# Sheet1.net
KiCad netlist of a schematic drawn in Altium Designer
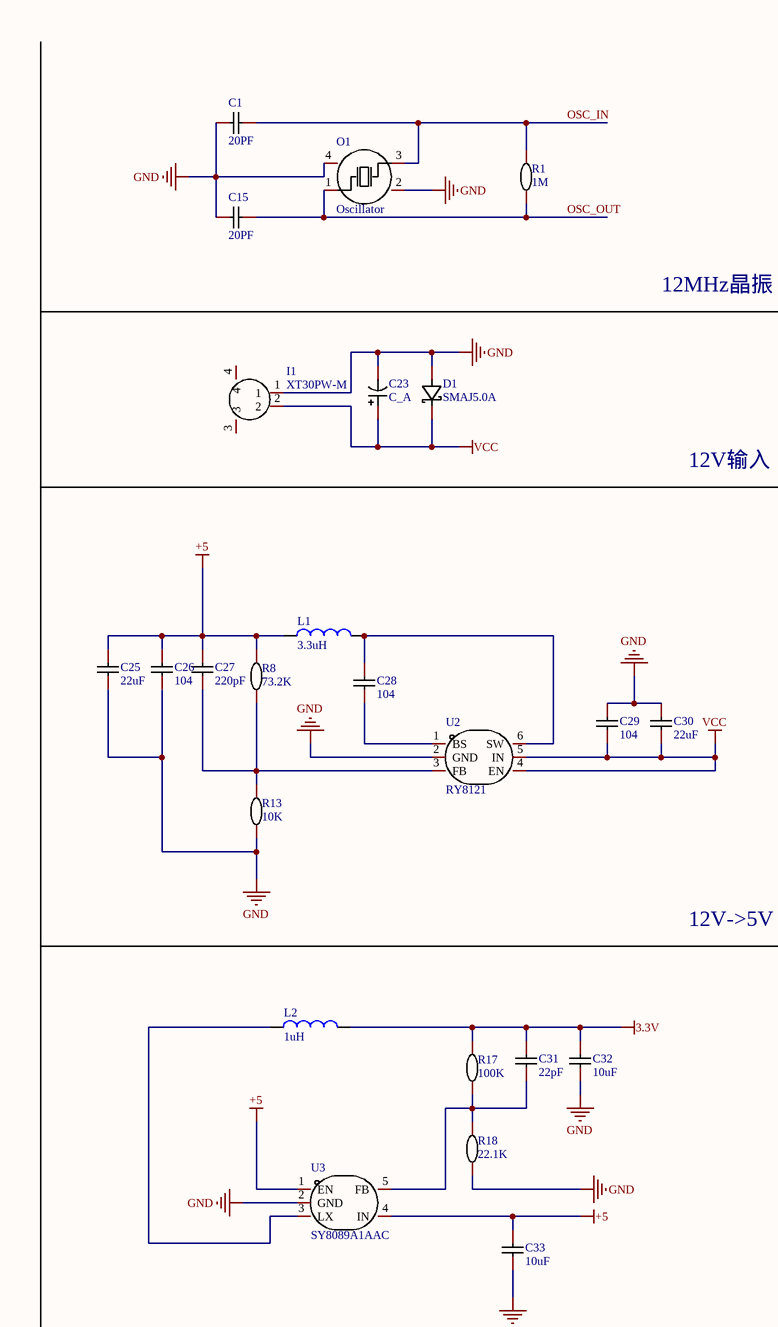
[diagram p0: Sheet1.SchDoc, top left]
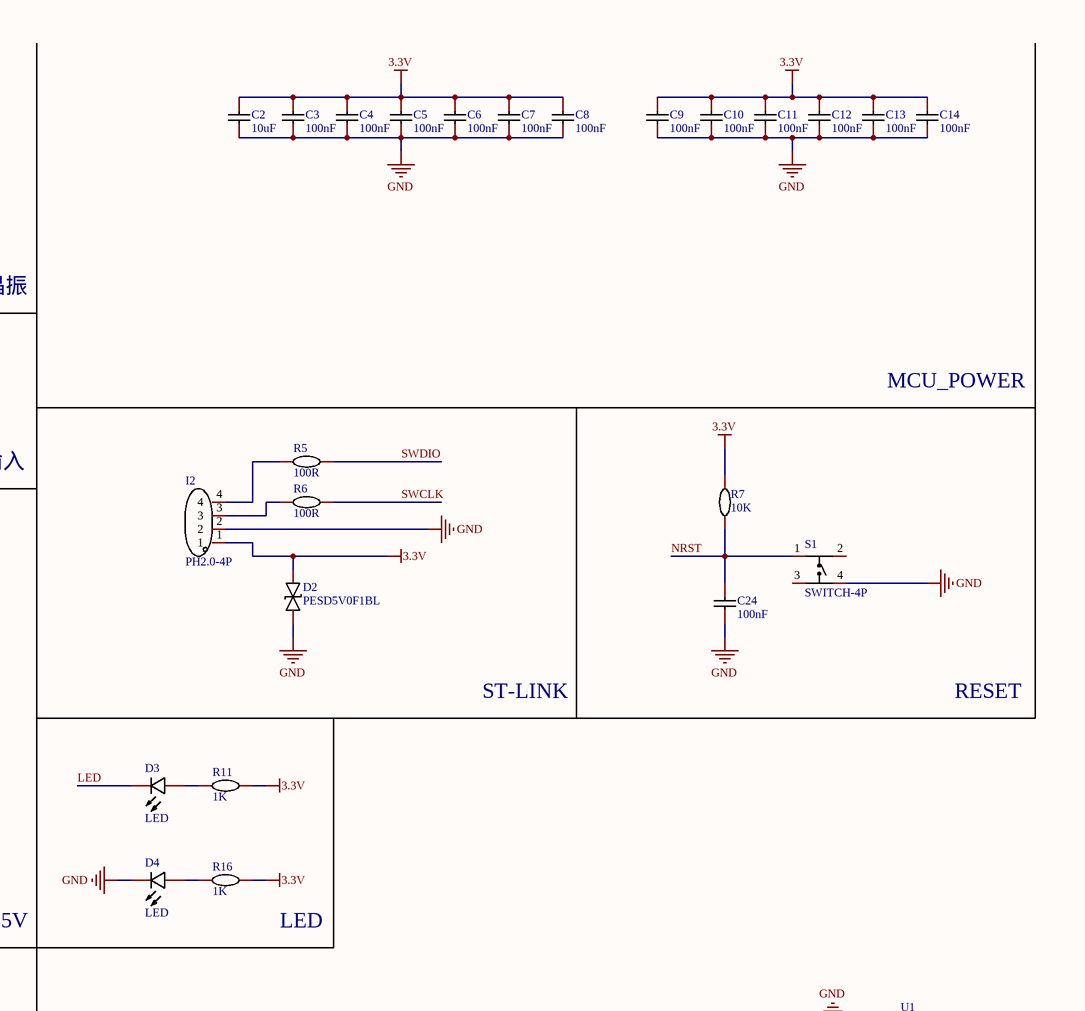
[diagram p1: Sheet1.SchDoc, top right]
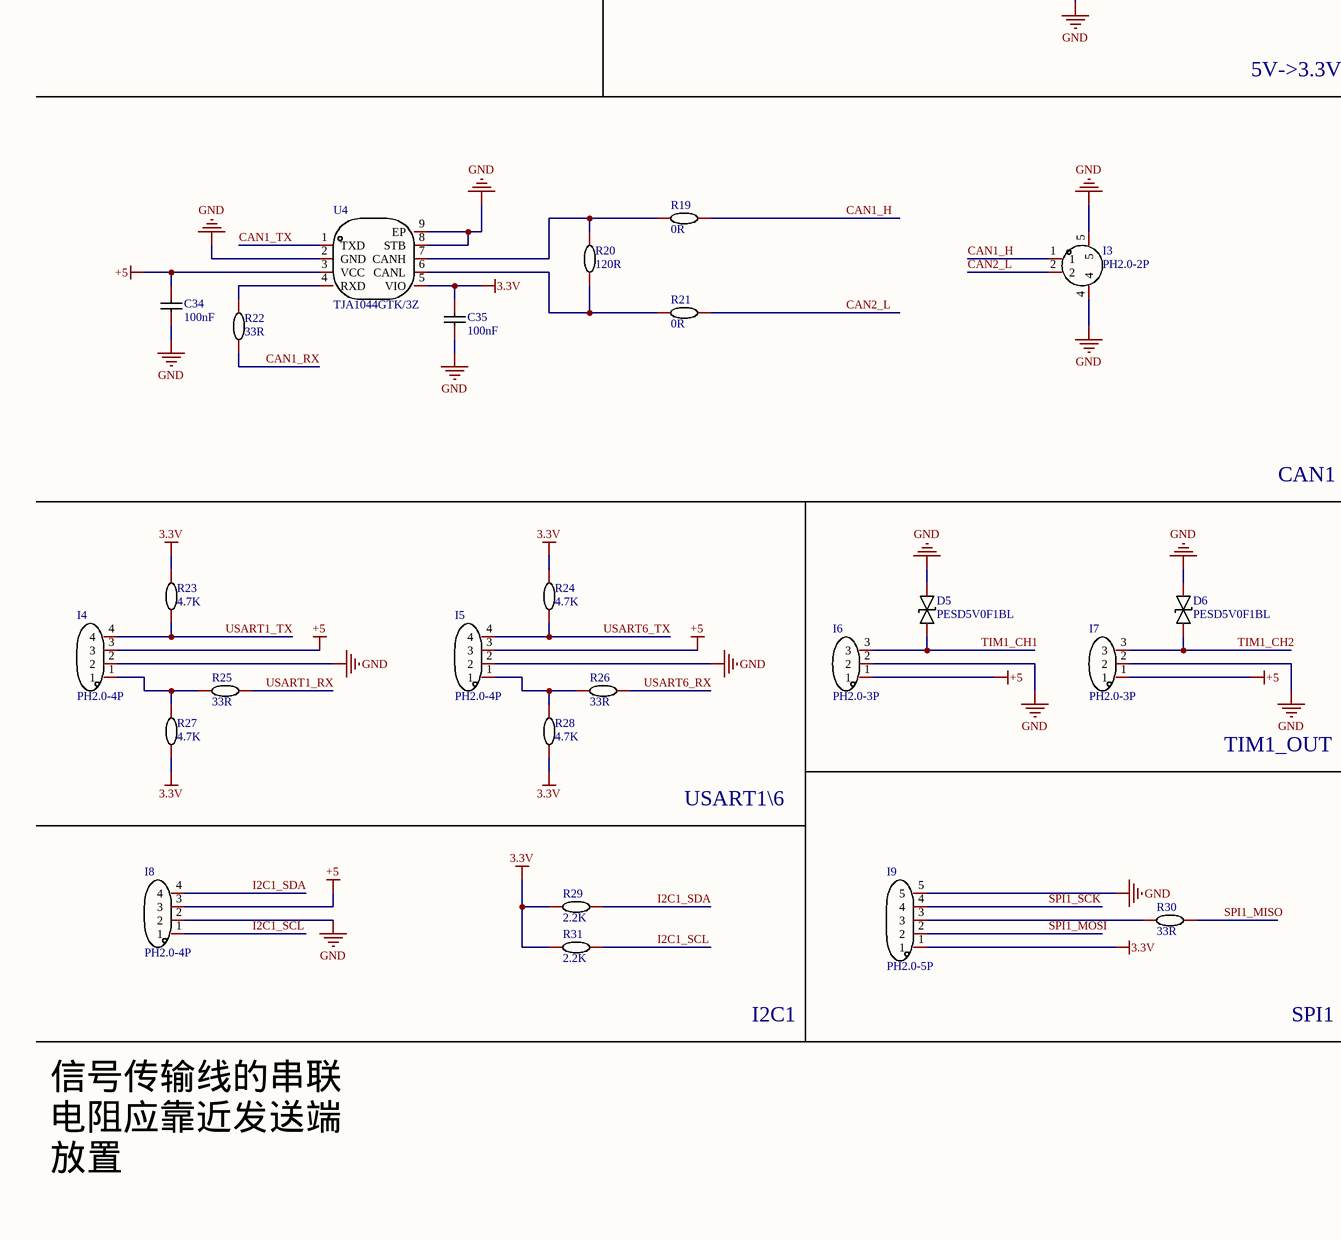
[diagram p2: Sheet1.SchDoc, bottom left]
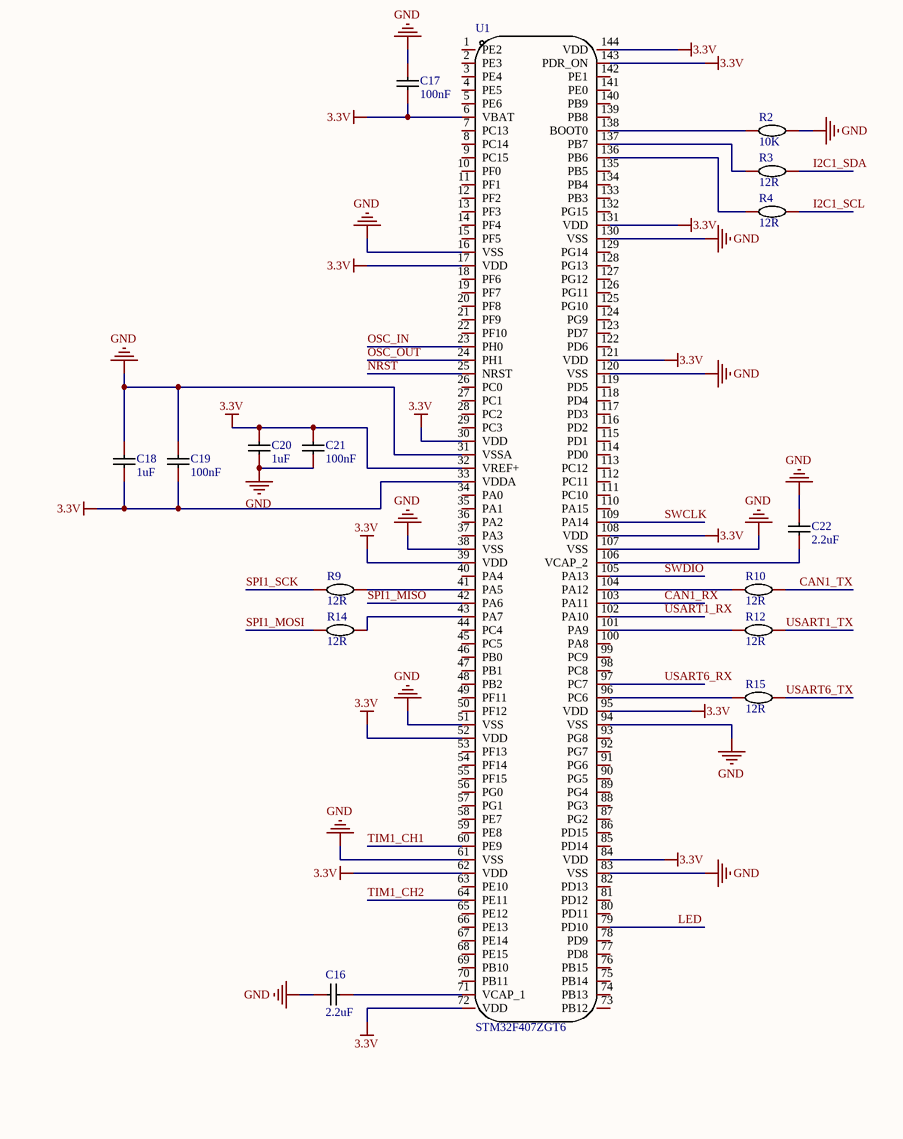
[diagram p3: Sheet1.SchDoc, bottom right]

(export (version "E")
  (design (tool "Eeschema 10.0.6"))
  (components
    (comp (ref "C1")
      (value "20PF")
      (footprint "C_0201")
      (description "贴片电容")
      (libsource (lib "My_Integrated_Library") (part "C"))
    )
    (comp (ref "C2")
      (value "10uF")
      (footprint "C_0201")
      (description "无极性贴片电容")
      (libsource (lib "My_Integrated_Library") (part "C"))
    )
    (comp (ref "C3")
      (value "100nF")
      (footprint "C_0201")
      (description "无极性贴片电容")
      (libsource (lib "My_Integrated_Library") (part "C"))
    )
    (comp (ref "C4")
      (value "100nF")
      (footprint "C_0201")
      (description "无极性贴片电容")
      (libsource (lib "My_Integrated_Library") (part "C"))
    )
    (comp (ref "C5")
      (value "100nF")
      (footprint "C_0201")
      (description "无极性贴片电容")
      (libsource (lib "My_Integrated_Library") (part "C"))
    )
    (comp (ref "C6")
      (value "100nF")
      (footprint "C_0201")
      (description "无极性贴片电容")
      (libsource (lib "My_Integrated_Library") (part "C"))
    )
    (comp (ref "C7")
      (value "100nF")
      (footprint "C_0201")
      (description "无极性贴片电容")
      (libsource (lib "My_Integrated_Library") (part "C"))
    )
    (comp (ref "C8")
      (value "100nF")
      (footprint "C_0201")
      (description "无极性贴片电容")
      (libsource (lib "My_Integrated_Library") (part "C"))
    )
    (comp (ref "C9")
      (value "100nF")
      (footprint "C_0201")
      (description "无极性贴片电容")
      (libsource (lib "My_Integrated_Library") (part "C"))
    )
    (comp (ref "C10")
      (value "100nF")
      (footprint "C_0201")
      (description "无极性贴片电容")
      (libsource (lib "My_Integrated_Library") (part "C"))
    )
    (comp (ref "C11")
      (value "100nF")
      (footprint "C_0201")
      (description "无极性贴片电容")
      (libsource (lib "My_Integrated_Library") (part "C"))
    )
    (comp (ref "C12")
      (value "100nF")
      (footprint "C_0201")
      (description "无极性贴片电容")
      (libsource (lib "My_Integrated_Library") (part "C"))
    )
    (comp (ref "C13")
      (value "100nF")
      (footprint "C_0201")
      (description "无极性贴片电容")
      (libsource (lib "My_Integrated_Library") (part "C"))
    )
    (comp (ref "C14")
      (value "100nF")
      (footprint "C_0201")
      (description "无极性贴片电容")
      (libsource (lib "My_Integrated_Library") (part "C"))
    )
    (comp (ref "C15")
      (value "20PF")
      (footprint "C_0201")
      (description "贴片电容")
      (libsource (lib "My_Integrated_Library") (part "C"))
    )
    (comp (ref "C16")
      (value "2.2uF")
      (footprint "C_0201")
      (description "无极性贴片电容")
      (libsource (lib "My_Integrated_Library") (part "C"))
    )
    (comp (ref "C17")
      (value "100nF")
      (footprint "C_0201")
      (description "无极性贴片电容")
      (libsource (lib "My_Integrated_Library") (part "C"))
    )
    (comp (ref "C18")
      (value "1uF")
      (footprint "C_0201")
      (description "无极性贴片电容")
      (libsource (lib "My_Integrated_Library") (part "C"))
    )
    (comp (ref "C19")
      (value "100nF")
      (footprint "C_0201")
      (description "无极性贴片电容")
      (libsource (lib "My_Integrated_Library") (part "C"))
    )
    (comp (ref "C20")
      (value "1uF")
      (footprint "C_0201")
      (description "无极性贴片电容")
      (libsource (lib "My_Integrated_Library") (part "C"))
    )
    (comp (ref "C21")
      (value "100nF")
      (footprint "C_0201")
      (description "无极性贴片电容")
      (libsource (lib "My_Integrated_Library") (part "C"))
    )
    (comp (ref "C22")
      (value "2.2uF")
      (footprint "C_0201")
      (description "无极性贴片电容")
      (libsource (lib "My_Integrated_Library") (part "C"))
    )
    (comp (ref "C23")
      (value "C_A")
      (footprint "C_8*10.5")
      (description "铝电解电容")
      (libsource (lib "My_Integrated_Library") (part "C_A"))
    )
    (comp (ref "C24")
      (value "100nF")
      (footprint "C_0201")
      (description "无极性贴片电容")
      (libsource (lib "My_Integrated_Library") (part "C"))
    )
    (comp (ref "C25")
      (value "22uF")
      (footprint "C_0402")
      (description "无极性贴片电容")
      (libsource (lib "My_Integrated_Library") (part "C"))
    )
    (comp (ref "C26")
      (value "104")
      (footprint "C_0402")
      (description "无极性贴片电容")
      (libsource (lib "My_Integrated_Library") (part "C"))
    )
    (comp (ref "C27")
      (value "220pF")
      (footprint "C_0402")
      (description "无极性贴片电容")
      (libsource (lib "My_Integrated_Library") (part "C"))
    )
    (comp (ref "C28")
      (value "104")
      (footprint "C_0402")
      (description "无极性贴片电容")
      (libsource (lib "My_Integrated_Library") (part "C"))
    )
    (comp (ref "C29")
      (value "104")
      (footprint "C_0402")
      (description "无极性贴片电容")
      (libsource (lib "My_Integrated_Library") (part "C"))
    )
    (comp (ref "C30")
      (value "22uF")
      (footprint "C_0402")
      (description "无极性贴片电容")
      (libsource (lib "My_Integrated_Library") (part "C"))
    )
    (comp (ref "C31")
      (value "22pF")
      (footprint "C_0603")
      (description "无极性贴片电容")
      (libsource (lib "My_Integrated_Library") (part "C"))
    )
    (comp (ref "C32")
      (value "10uF")
      (footprint "C_0603")
      (description "无极性贴片电容")
      (libsource (lib "My_Integrated_Library") (part "C"))
    )
    (comp (ref "C33")
      (value "10uF")
      (footprint "C_0603")
      (description "无极性贴片电容")
      (libsource (lib "My_Integrated_Library") (part "C"))
    )
    (comp (ref "C34")
      (value "100nF")
      (footprint "C_0402")
      (description "无极性贴片电容")
      (libsource (lib "My_Integrated_Library") (part "C"))
    )
    (comp (ref "C35")
      (value "100nF")
      (footprint "C_0402")
      (description "无极性贴片电容")
      (libsource (lib "My_Integrated_Library") (part "C"))
    )
    (comp (ref "D1")
      (value "SMAJ5.0A")
      (footprint "SMAJ5.0A")
      (description "TVS")
      (libsource (lib "My_Integrated_Library") (part "SMAJ5.0A"))
    )
    (comp (ref "D2")
      (value "PESD5V0F1BL")
      (footprint "PESD5V0F1BL")
      (description "双向TVS")
      (libsource (lib "My_Integrated_Library") (part "PESD5V0F1BL"))
    )
    (comp (ref "D3")
      (value "LED")
      (footprint "LED_0603")
      (description "发光二极管")
      (libsource (lib "My_Integrated_Library") (part "LED"))
    )
    (comp (ref "D4")
      (value "LED")
      (footprint "LED_0603")
      (description "发光二极管")
      (libsource (lib "My_Integrated_Library") (part "LED"))
    )
    (comp (ref "D5")
      (value "PESD5V0F1BL")
      (footprint "PESD5V0F1BL")
      (description "双向TVS")
      (libsource (lib "My_Integrated_Library") (part "PESD5V0F1BL"))
    )
    (comp (ref "D6")
      (value "PESD5V0F1BL")
      (footprint "PESD5V0F1BL")
      (description "双向TVS")
      (libsource (lib "My_Integrated_Library") (part "PESD5V0F1BL"))
    )
    (comp (ref "I1")
      (value "XT30PW-M")
      (footprint "XT30PW-M")
      (description "卧式公头")
      (libsource (lib "My_Integrated_Library") (part "XT30PW-M"))
    )
    (comp (ref "I2")
      (value "PH2.0-4P")
      (footprint "PH2.0-4P")
      (libsource (lib "My_Integrated_Library") (part "PH2.0-4P"))
    )
    (comp (ref "I3")
      (value "PH2.0-2P")
      (footprint "PH2.0-2P")
      (description "卧贴")
      (libsource (lib "My_Integrated_Library") (part "PH2.0-2P"))
    )
    (comp (ref "I4")
      (value "PH2.0-4P")
      (footprint "PH2.0-4P")
      (libsource (lib "My_Integrated_Library") (part "PH2.0-4P"))
    )
    (comp (ref "I5")
      (value "PH2.0-4P")
      (footprint "PH2.0-4P")
      (libsource (lib "My_Integrated_Library") (part "PH2.0-4P"))
    )
    (comp (ref "I6")
      (value "PH2.0-3P")
      (footprint "PH2.0-3P")
      (description "PH3.0-3P弯插")
      (libsource (lib "My_Integrated_Library") (part "PH2.0-3P"))
    )
    (comp (ref "I7")
      (value "PH2.0-3P")
      (footprint "PH2.0-3P")
      (description "PH3.0-3P弯插")
      (libsource (lib "My_Integrated_Library") (part "PH2.0-3P"))
    )
    (comp (ref "I8")
      (value "PH2.0-4P")
      (footprint "PH2.0-4P")
      (libsource (lib "My_Integrated_Library") (part "PH2.0-4P"))
    )
    (comp (ref "I9")
      (value "PH2.0-5P")
      (footprint "PH2.0-5P")
      (description "弯插")
      (libsource (lib "My_Integrated_Library") (part "PH2.0-5P"))
    )
    (comp (ref "L1")
      (value "3.3uH")
      (footprint "L_0402")
      (description "SMD电感4.2*4.2*1.8")
      (libsource (lib "My_Integrated_Library") (part "L"))
    )
    (comp (ref "L2")
      (value "1uH")
      (footprint "L_0402")
      (description "SMD电感4.2*4.2*1.8")
      (libsource (lib "My_Integrated_Library") (part "L"))
    )
    (comp (ref "O1")
      (value "Oscillator")
      (footprint "Oscillator")
      (description "晶振")
      (libsource (lib "My_Integrated_Library") (part "Oscillator"))
    )
    (comp (ref "R1")
      (value "1M")
      (footprint "R_0201")
      (description "电阻")
      (libsource (lib "My_Integrated_Library") (part "R"))
    )
    (comp (ref "R2")
      (value "10K")
      (footprint "R_0402")
      (description "贴片电阻")
      (libsource (lib "My_Integrated_Library") (part "R"))
    )
    (comp (ref "R3")
      (value "12R")
      (footprint "R_0402")
      (description "贴片电阻")
      (libsource (lib "My_Integrated_Library") (part "R"))
    )
    (comp (ref "R4")
      (value "12R")
      (footprint "R_0402")
      (description "贴片电阻")
      (libsource (lib "My_Integrated_Library") (part "R"))
    )
    (comp (ref "R5")
      (value "100R")
      (footprint "R_0201")
      (description "贴片电阻")
      (libsource (lib "My_Integrated_Library") (part "R"))
    )
    (comp (ref "R6")
      (value "100R")
      (footprint "R_0201")
      (description "贴片电阻")
      (libsource (lib "My_Integrated_Library") (part "R"))
    )
    (comp (ref "R7")
      (value "10K")
      (footprint "R_0201")
      (description "贴片电阻")
      (libsource (lib "My_Integrated_Library") (part "R"))
    )
    (comp (ref "R8")
      (value "73.2K")
      (footprint "R_0603")
      (description "贴片电阻")
      (libsource (lib "My_Integrated_Library") (part "R"))
    )
    (comp (ref "R9")
      (value "12R")
      (footprint "R_0402")
      (description "贴片电阻")
      (libsource (lib "My_Integrated_Library") (part "R"))
    )
    (comp (ref "R10")
      (value "12R")
      (footprint "R_0402")
      (description "贴片电阻")
      (libsource (lib "My_Integrated_Library") (part "R"))
    )
    (comp (ref "R11")
      (value "1K")
      (footprint "R_0603")
      (description "贴片电阻")
      (libsource (lib "My_Integrated_Library") (part "R"))
    )
    (comp (ref "R12")
      (value "12R")
      (footprint "R_0402")
      (description "贴片电阻")
      (libsource (lib "My_Integrated_Library") (part "R"))
    )
    (comp (ref "R13")
      (value "10K")
      (footprint "R_0603")
      (description "贴片电阻")
      (libsource (lib "My_Integrated_Library") (part "R"))
    )
    (comp (ref "R14")
      (value "12R")
      (footprint "R_0402")
      (description "贴片电阻")
      (libsource (lib "My_Integrated_Library") (part "R"))
    )
    (comp (ref "R15")
      (value "12R")
      (footprint "R_0402")
      (description "贴片电阻")
      (libsource (lib "My_Integrated_Library") (part "R"))
    )
    (comp (ref "R16")
      (value "1K")
      (footprint "R_0603")
      (description "贴片电阻")
      (libsource (lib "My_Integrated_Library") (part "R"))
    )
    (comp (ref "R17")
      (value "100K")
      (footprint "R_0603")
      (description "贴片电阻")
      (libsource (lib "My_Integrated_Library") (part "R"))
    )
    (comp (ref "R18")
      (value "22.1K")
      (footprint "R_0603")
      (description "贴片电阻")
      (libsource (lib "My_Integrated_Library") (part "R"))
    )
    (comp (ref "R19")
      (value "0R")
      (footprint "R_0402")
      (description "贴片电阻")
      (libsource (lib "My_Integrated_Library") (part "R"))
    )
    (comp (ref "R20")
      (value "120R")
      (footprint "R_0402")
      (description "贴片电阻")
      (libsource (lib "My_Integrated_Library") (part "R"))
    )
    (comp (ref "R21")
      (value "0R")
      (footprint "R_0402")
      (description "贴片电阻")
      (libsource (lib "My_Integrated_Library") (part "R"))
    )
    (comp (ref "R22")
      (value "33R")
      (footprint "R_0402")
      (description "贴片电阻")
      (libsource (lib "My_Integrated_Library") (part "R"))
    )
    (comp (ref "R23")
      (value "4.7K")
      (footprint "R_0402")
      (description "贴片电阻")
      (libsource (lib "My_Integrated_Library") (part "R"))
    )
    (comp (ref "R24")
      (value "4.7K")
      (footprint "R_0402")
      (description "贴片电阻")
      (libsource (lib "My_Integrated_Library") (part "R"))
    )
    (comp (ref "R25")
      (value "33R")
      (footprint "R_0402")
      (description "贴片电阻")
      (libsource (lib "My_Integrated_Library") (part "R"))
    )
    (comp (ref "R26")
      (value "33R")
      (footprint "R_0402")
      (description "贴片电阻")
      (libsource (lib "My_Integrated_Library") (part "R"))
    )
    (comp (ref "R27")
      (value "4.7K")
      (footprint "R_0402")
      (description "贴片电阻")
      (libsource (lib "My_Integrated_Library") (part "R"))
    )
    (comp (ref "R28")
      (value "4.7K")
      (footprint "R_0402")
      (description "贴片电阻")
      (libsource (lib "My_Integrated_Library") (part "R"))
    )
    (comp (ref "R29")
      (value "2.2K")
      (footprint "R_0402")
      (description "贴片电阻")
      (libsource (lib "My_Integrated_Library") (part "R"))
    )
    (comp (ref "R30")
      (value "33R")
      (footprint "R_0402")
      (description "贴片电阻")
      (libsource (lib "My_Integrated_Library") (part "R"))
    )
    (comp (ref "R31")
      (value "2.2K")
      (footprint "R_0402")
      (description "贴片电阻")
      (libsource (lib "My_Integrated_Library") (part "R"))
    )
    (comp (ref "S1")
      (value "SWITCH-4P")
      (footprint "SWITCH-4P")
      (libsource (lib "My_Integrated_Library") (part "SWITCH-4P"))
    )
    (comp (ref "U1")
      (value "STM32F407ZGT6")
      (footprint "STM32F407ZGT6")
      (libsource (lib "My_Integrated_Library") (part "STM32F407ZGT6"))
    )
    (comp (ref "U2")
      (value "RY8121")
      (footprint "RY8121")
      (description "DC-DC")
      (libsource (lib "My_Integrated_Library") (part "RY8121"))
    )
    (comp (ref "U3")
      (value "SY8089A1AAC")
      (footprint "SY8089A1AAC")
      (description "DC-DC")
      (libsource (lib "My_Integrated_Library") (part "SY8089A1AAC"))
    )
    (comp (ref "U4")
      (value "TJA1044GTK/3Z")
      (footprint "TJA1044GTK/3Z")
      (description "CAN")
      (libsource (lib "My_Integrated_Library") (part "TJA1044GTK/3Z"))
    )
  )
  (nets
    (net (code "1") (name "+5") (class "Default")
      (node (ref "C25") (pin "2") (pinfunction "2_2") (pintype "passive"))
      (node (ref "C26") (pin "2") (pinfunction "2_2") (pintype "passive"))
      (node (ref "C27") (pin "2") (pinfunction "2_2") (pintype "passive"))
      (node (ref "C33") (pin "2") (pinfunction "2_2") (pintype "passive"))
      (node (ref "C34") (pin "2") (pinfunction "2_2") (pintype "passive"))
      (node (ref "I4") (pin "3") (pinfunction "3_3") (pintype "passive"))
      (node (ref "I5") (pin "3") (pinfunction "3_3") (pintype "passive"))
      (node (ref "I6") (pin "1") (pinfunction "1_1") (pintype "passive"))
      (node (ref "I7") (pin "1") (pinfunction "1_1") (pintype "passive"))
      (node (ref "I8") (pin "3") (pinfunction "3_3") (pintype "passive"))
      (node (ref "L1") (pin "1") (pinfunction "1_1") (pintype "passive"))
      (node (ref "R8") (pin "2") (pinfunction "2_2") (pintype "passive"))
      (node (ref "U3") (pin "1") (pinfunction "EN_1") (pintype "passive"))
      (node (ref "U3") (pin "4") (pinfunction "IN_4") (pintype "passive"))
      (node (ref "U4") (pin "3") (pinfunction "VCC_3") (pintype "passive"))
    )
    (net (code "2") (name "/CAN1_H") (class "Default")
      (node (ref "I3") (pin "1") (pinfunction "1_1") (pintype "passive"))
      (node (ref "R19") (pin "1") (pinfunction "1_1") (pintype "passive"))
    )
    (net (code "3") (name "/CAN1_RX") (class "Default")
      (node (ref "R22") (pin "1") (pinfunction "1_1") (pintype "passive"))
      (node (ref "U1") (pin "103") (pinfunction "PA11_103") (pintype "passive"))
    )
    (net (code "4") (name "/CAN1_TX") (class "Default")
      (node (ref "R10") (pin "1") (pinfunction "1_1") (pintype "passive"))
      (node (ref "U4") (pin "1") (pinfunction "TXD_1") (pintype "passive"))
    )
    (net (code "5") (name "/CAN2_L") (class "Default")
      (node (ref "I3") (pin "2") (pinfunction "2_2") (pintype "passive"))
      (node (ref "R21") (pin "1") (pinfunction "1_1") (pintype "passive"))
    )
    (net (code "6") (name "/I2C1_SCL") (class "Default")
      (node (ref "I8") (pin "1") (pinfunction "1_1") (pintype "passive"))
      (node (ref "R31") (pin "1") (pinfunction "1_1") (pintype "passive"))
      (node (ref "R4") (pin "1") (pinfunction "1_1") (pintype "passive"))
    )
    (net (code "7") (name "/I2C1_SDA") (class "Default")
      (node (ref "I8") (pin "4") (pinfunction "4_4") (pintype "passive"))
      (node (ref "R29") (pin "1") (pinfunction "1_1") (pintype "passive"))
      (node (ref "R3") (pin "1") (pinfunction "1_1") (pintype "passive"))
    )
    (net (code "8") (name "/LED") (class "Default")
      (node (ref "D3") (pin "1") (pinfunction "K_1") (pintype "passive"))
      (node (ref "U1") (pin "79") (pinfunction "PD10_79") (pintype "passive"))
    )
    (net (code "9") (name "/NRST") (class "Default")
      (node (ref "C24") (pin "2") (pinfunction "2_2") (pintype "passive"))
      (node (ref "R7") (pin "1") (pinfunction "1_1") (pintype "passive"))
      (node (ref "S1") (pin "1") (pinfunction "1_1") (pintype "passive"))
      (node (ref "U1") (pin "25") (pinfunction "NRST_25") (pintype "passive"))
    )
    (net (code "10") (name "/OSC_IN") (class "Default")
      (node (ref "C1") (pin "2") (pinfunction "2_2") (pintype "passive"))
      (node (ref "O1") (pin "3") (pinfunction "OSC2_3") (pintype "passive"))
      (node (ref "R1") (pin "2") (pinfunction "2_2") (pintype "passive"))
      (node (ref "U1") (pin "23") (pinfunction "PH0_23") (pintype "passive"))
    )
    (net (code "11") (name "/OSC_OUT") (class "Default")
      (node (ref "C15") (pin "2") (pinfunction "2_2") (pintype "passive"))
      (node (ref "O1") (pin "1") (pinfunction "OSC1_1") (pintype "passive"))
      (node (ref "R1") (pin "1") (pinfunction "1_1") (pintype "passive"))
      (node (ref "U1") (pin "24") (pinfunction "PH1_24") (pintype "passive"))
    )
    (net (code "12") (name "/SPI1_MISO") (class "Default")
      (node (ref "R30") (pin "2") (pinfunction "2_2") (pintype "passive"))
      (node (ref "U1") (pin "42") (pinfunction "PA6_42") (pintype "passive"))
    )
    (net (code "13") (name "/SPI1_MOSI") (class "Default")
      (node (ref "I9") (pin "2") (pinfunction "2_2") (pintype "passive"))
      (node (ref "R14") (pin "2") (pinfunction "2_2") (pintype "passive"))
    )
    (net (code "14") (name "/SPI1_SCK") (class "Default")
      (node (ref "I9") (pin "4") (pinfunction "4_4") (pintype "passive"))
      (node (ref "R9") (pin "2") (pinfunction "2_2") (pintype "passive"))
    )
    (net (code "15") (name "/SWCLK") (class "Default")
      (node (ref "R6") (pin "2") (pinfunction "2_2") (pintype "passive"))
      (node (ref "U1") (pin "109") (pinfunction "PA14_109") (pintype "passive"))
    )
    (net (code "16") (name "/SWDIO") (class "Default")
      (node (ref "R5") (pin "2") (pinfunction "2_2") (pintype "passive"))
      (node (ref "U1") (pin "105") (pinfunction "PA13_105") (pintype "passive"))
    )
    (net (code "17") (name "/TIM1_CH1") (class "Default")
      (node (ref "D5") (pin "1") (pinfunction "1_1") (pintype "passive"))
      (node (ref "I6") (pin "3") (pinfunction "3_3") (pintype "passive"))
      (node (ref "U1") (pin "60") (pinfunction "PE9_60") (pintype "passive"))
    )
    (net (code "18") (name "/TIM1_CH2") (class "Default")
      (node (ref "D6") (pin "1") (pinfunction "1_1") (pintype "passive"))
      (node (ref "I7") (pin "3") (pinfunction "3_3") (pintype "passive"))
      (node (ref "U1") (pin "64") (pinfunction "PE11_64") (pintype "passive"))
    )
    (net (code "19") (name "/USART1_RX") (class "Default")
      (node (ref "R25") (pin "2") (pinfunction "2_2") (pintype "passive"))
      (node (ref "U1") (pin "102") (pinfunction "PA10_102") (pintype "passive"))
    )
    (net (code "20") (name "/USART1_TX") (class "Default")
      (node (ref "I4") (pin "4") (pinfunction "4_4") (pintype "passive"))
      (node (ref "R12") (pin "1") (pinfunction "1_1") (pintype "passive"))
      (node (ref "R23") (pin "1") (pinfunction "1_1") (pintype "passive"))
    )
    (net (code "21") (name "/USART6_RX") (class "Default")
      (node (ref "R26") (pin "2") (pinfunction "2_2") (pintype "passive"))
      (node (ref "U1") (pin "97") (pinfunction "PC7_97") (pintype "passive"))
    )
    (net (code "22") (name "/USART6_TX") (class "Default")
      (node (ref "I5") (pin "4") (pinfunction "4_4") (pintype "passive"))
      (node (ref "R15") (pin "1") (pinfunction "1_1") (pintype "passive"))
      (node (ref "R24") (pin "1") (pinfunction "1_1") (pintype "passive"))
    )
    (net (code "23") (name "3.3V") (class "Default")
      (node (ref "C10") (pin "1") (pinfunction "1_1") (pintype "passive"))
      (node (ref "C11") (pin "1") (pinfunction "1_1") (pintype "passive"))
      (node (ref "C12") (pin "1") (pinfunction "1_1") (pintype "passive"))
      (node (ref "C13") (pin "1") (pinfunction "1_1") (pintype "passive"))
      (node (ref "C14") (pin "1") (pinfunction "1_1") (pintype "passive"))
      (node (ref "C17") (pin "2") (pinfunction "2_2") (pintype "passive"))
      (node (ref "C18") (pin "1") (pinfunction "1_1") (pintype "passive"))
      (node (ref "C19") (pin "1") (pinfunction "1_1") (pintype "passive"))
      (node (ref "C2") (pin "1") (pinfunction "1_1") (pintype "passive"))
      (node (ref "C20") (pin "2") (pinfunction "2_2") (pintype "passive"))
      (node (ref "C21") (pin "2") (pinfunction "2_2") (pintype "passive"))
      (node (ref "C3") (pin "1") (pinfunction "1_1") (pintype "passive"))
      (node (ref "C31") (pin "2") (pinfunction "2_2") (pintype "passive"))
      (node (ref "C32") (pin "2") (pinfunction "2_2") (pintype "passive"))
      (node (ref "C35") (pin "2") (pinfunction "2_2") (pintype "passive"))
      (node (ref "C4") (pin "1") (pinfunction "1_1") (pintype "passive"))
      (node (ref "C5") (pin "1") (pinfunction "1_1") (pintype "passive"))
      (node (ref "C6") (pin "1") (pinfunction "1_1") (pintype "passive"))
      (node (ref "C7") (pin "1") (pinfunction "1_1") (pintype "passive"))
      (node (ref "C8") (pin "1") (pinfunction "1_1") (pintype "passive"))
      (node (ref "C9") (pin "1") (pinfunction "1_1") (pintype "passive"))
      (node (ref "D2") (pin "2") (pinfunction "2_2") (pintype "passive"))
      (node (ref "I2") (pin "1") (pinfunction "1_1") (pintype "passive"))
      (node (ref "I9") (pin "1") (pinfunction "1_1") (pintype "passive"))
      (node (ref "L2") (pin "2") (pinfunction "2_2") (pintype "passive"))
      (node (ref "R11") (pin "2") (pinfunction "2_2") (pintype "passive"))
      (node (ref "R16") (pin "2") (pinfunction "2_2") (pintype "passive"))
      (node (ref "R17") (pin "2") (pinfunction "2_2") (pintype "passive"))
      (node (ref "R23") (pin "2") (pinfunction "2_2") (pintype "passive"))
      (node (ref "R24") (pin "2") (pinfunction "2_2") (pintype "passive"))
      (node (ref "R27") (pin "1") (pinfunction "1_1") (pintype "passive"))
      (node (ref "R28") (pin "1") (pinfunction "1_1") (pintype "passive"))
      (node (ref "R29") (pin "2") (pinfunction "2_2") (pintype "passive"))
      (node (ref "R31") (pin "2") (pinfunction "2_2") (pintype "passive"))
      (node (ref "R7") (pin "2") (pinfunction "2_2") (pintype "passive"))
      (node (ref "U1") (pin "108") (pinfunction "VDD_108") (pintype "passive"))
      (node (ref "U1") (pin "121") (pinfunction "VDD_121") (pintype "passive"))
      (node (ref "U1") (pin "131") (pinfunction "VDD_131") (pintype "passive"))
      (node (ref "U1") (pin "143") (pinfunction "PDR_ON_143") (pintype "passive"))
      (node (ref "U1") (pin "144") (pinfunction "VDD_144") (pintype "passive"))
      (node (ref "U1") (pin "17") (pinfunction "VDD_17") (pintype "passive"))
      (node (ref "U1") (pin "30") (pinfunction "VDD_30") (pintype "passive"))
      (node (ref "U1") (pin "32") (pinfunction "VREF+_32") (pintype "passive"))
      (node (ref "U1") (pin "33") (pinfunction "VDDA_33") (pintype "passive"))
      (node (ref "U1") (pin "39") (pinfunction "VDD_39") (pintype "passive"))
      (node (ref "U1") (pin "52") (pinfunction "VDD_52") (pintype "passive"))
      (node (ref "U1") (pin "6") (pinfunction "VBAT_6") (pintype "passive"))
      (node (ref "U1") (pin "62") (pinfunction "VDD_62") (pintype "passive"))
      (node (ref "U1") (pin "72") (pinfunction "VDD_72") (pintype "passive"))
      (node (ref "U1") (pin "84") (pinfunction "VDD_84") (pintype "passive"))
      (node (ref "U1") (pin "95") (pinfunction "VDD_95") (pintype "passive"))
      (node (ref "U4") (pin "5") (pinfunction "VIO_5") (pintype "passive"))
    )
    (net (code "24") (name "GND") (class "Default")
      (node (ref "C1") (pin "1") (pinfunction "1_1") (pintype "passive"))
      (node (ref "C10") (pin "2") (pinfunction "2_2") (pintype "passive"))
      (node (ref "C11") (pin "2") (pinfunction "2_2") (pintype "passive"))
      (node (ref "C12") (pin "2") (pinfunction "2_2") (pintype "passive"))
      (node (ref "C13") (pin "2") (pinfunction "2_2") (pintype "passive"))
      (node (ref "C14") (pin "2") (pinfunction "2_2") (pintype "passive"))
      (node (ref "C15") (pin "1") (pinfunction "1_1") (pintype "passive"))
      (node (ref "C16") (pin "1") (pinfunction "1_1") (pintype "passive"))
      (node (ref "C17") (pin "1") (pinfunction "1_1") (pintype "passive"))
      (node (ref "C18") (pin "2") (pinfunction "2_2") (pintype "passive"))
      (node (ref "C19") (pin "2") (pinfunction "2_2") (pintype "passive"))
      (node (ref "C2") (pin "2") (pinfunction "2_2") (pintype "passive"))
      (node (ref "C20") (pin "1") (pinfunction "1_1") (pintype "passive"))
      (node (ref "C21") (pin "1") (pinfunction "1_1") (pintype "passive"))
      (node (ref "C22") (pin "2") (pinfunction "2_2") (pintype "passive"))
      (node (ref "C23") (pin "2") (pinfunction "2_2") (pintype "passive"))
      (node (ref "C24") (pin "1") (pinfunction "1_1") (pintype "passive"))
      (node (ref "C25") (pin "1") (pinfunction "1_1") (pintype "passive"))
      (node (ref "C26") (pin "1") (pinfunction "1_1") (pintype "passive"))
      (node (ref "C29") (pin "2") (pinfunction "2_2") (pintype "passive"))
      (node (ref "C3") (pin "2") (pinfunction "2_2") (pintype "passive"))
      (node (ref "C30") (pin "2") (pinfunction "2_2") (pintype "passive"))
      (node (ref "C32") (pin "1") (pinfunction "1_1") (pintype "passive"))
      (node (ref "C33") (pin "1") (pinfunction "1_1") (pintype "passive"))
      (node (ref "C34") (pin "1") (pinfunction "1_1") (pintype "passive"))
      (node (ref "C35") (pin "1") (pinfunction "1_1") (pintype "passive"))
      (node (ref "C4") (pin "2") (pinfunction "2_2") (pintype "passive"))
      (node (ref "C5") (pin "2") (pinfunction "2_2") (pintype "passive"))
      (node (ref "C6") (pin "2") (pinfunction "2_2") (pintype "passive"))
      (node (ref "C7") (pin "2") (pinfunction "2_2") (pintype "passive"))
      (node (ref "C8") (pin "2") (pinfunction "2_2") (pintype "passive"))
      (node (ref "C9") (pin "2") (pinfunction "2_2") (pintype "passive"))
      (node (ref "D1") (pin "2") (pinfunction "A_2") (pintype "passive"))
      (node (ref "D2") (pin "1") (pinfunction "1_1") (pintype "passive"))
      (node (ref "D4") (pin "1") (pinfunction "K_1") (pintype "passive"))
      (node (ref "D5") (pin "2") (pinfunction "2_2") (pintype "passive"))
      (node (ref "D6") (pin "2") (pinfunction "2_2") (pintype "passive"))
      (node (ref "I1") (pin "1") (pinfunction "1_1") (pintype "passive"))
      (node (ref "I2") (pin "2") (pinfunction "2_2") (pintype "passive"))
      (node (ref "I3") (pin "4") (pinfunction "4_4") (pintype "passive"))
      (node (ref "I3") (pin "5") (pinfunction "5_5") (pintype "passive"))
      (node (ref "I4") (pin "2") (pinfunction "2_2") (pintype "passive"))
      (node (ref "I5") (pin "2") (pinfunction "2_2") (pintype "passive"))
      (node (ref "I6") (pin "2") (pinfunction "2_2") (pintype "passive"))
      (node (ref "I7") (pin "2") (pinfunction "2_2") (pintype "passive"))
      (node (ref "I8") (pin "2") (pinfunction "2_2") (pintype "passive"))
      (node (ref "I9") (pin "5") (pinfunction "5_5") (pintype "passive"))
      (node (ref "O1") (pin "2") (pinfunction "GND_2") (pintype "passive"))
      (node (ref "O1") (pin "4") (pinfunction "GND_4") (pintype "passive"))
      (node (ref "R13") (pin "1") (pinfunction "1_1") (pintype "passive"))
      (node (ref "R18") (pin "1") (pinfunction "1_1") (pintype "passive"))
      (node (ref "R2") (pin "1") (pinfunction "1_1") (pintype "passive"))
      (node (ref "S1") (pin "4") (pinfunction "4_4") (pintype "passive"))
      (node (ref "U1") (pin "107") (pinfunction "VSS_107") (pintype "passive"))
      (node (ref "U1") (pin "120") (pinfunction "VSS_120") (pintype "passive"))
      (node (ref "U1") (pin "130") (pinfunction "VSS_130") (pintype "passive"))
      (node (ref "U1") (pin "16") (pinfunction "VSS_16") (pintype "passive"))
      (node (ref "U1") (pin "31") (pinfunction "VSSA_31") (pintype "passive"))
      (node (ref "U1") (pin "38") (pinfunction "VSS_38") (pintype "passive"))
      (node (ref "U1") (pin "51") (pinfunction "VSS_51") (pintype "passive"))
      (node (ref "U1") (pin "61") (pinfunction "VSS_61") (pintype "passive"))
      (node (ref "U1") (pin "83") (pinfunction "VSS_83") (pintype "passive"))
      (node (ref "U1") (pin "94") (pinfunction "VSS_94") (pintype "passive"))
      (node (ref "U2") (pin "2") (pinfunction "GND_2") (pintype "passive"))
      (node (ref "U3") (pin "2") (pinfunction "GND_2") (pintype "passive"))
      (node (ref "U4") (pin "2") (pinfunction "GND_2") (pintype "passive"))
      (node (ref "U4") (pin "8") (pinfunction "STB_8") (pintype "passive"))
      (node (ref "U4") (pin "9") (pinfunction "EP_9") (pintype "passive"))
    )
    (net (code "25") (name "Net-(D3-A)") (class "Default")
      (node (ref "D3") (pin "2") (pinfunction "A_2") (pintype "passive"))
      (node (ref "R11") (pin "1") (pinfunction "1_1") (pintype "passive"))
    )
    (net (code "26") (name "Net-(D4-A)") (class "Default")
      (node (ref "D4") (pin "2") (pinfunction "A_2") (pintype "passive"))
      (node (ref "R16") (pin "1") (pinfunction "1_1") (pintype "passive"))
    )
    (net (code "27") (name "Net-(I2-Pad3)") (class "Default")
      (node (ref "I2") (pin "3") (pinfunction "3_3") (pintype "passive"))
      (node (ref "R6") (pin "1") (pinfunction "1_1") (pintype "passive"))
    )
    (net (code "28") (name "Net-(I2-Pad4)") (class "Default")
      (node (ref "I2") (pin "4") (pinfunction "4_4") (pintype "passive"))
      (node (ref "R5") (pin "1") (pinfunction "1_1") (pintype "passive"))
    )
    (net (code "29") (name "Net-(I4-Pad1)") (class "Default")
      (node (ref "I4") (pin "1") (pinfunction "1_1") (pintype "passive"))
      (node (ref "R25") (pin "1") (pinfunction "1_1") (pintype "passive"))
      (node (ref "R27") (pin "2") (pinfunction "2_2") (pintype "passive"))
    )
    (net (code "30") (name "Net-(I5-Pad1)") (class "Default")
      (node (ref "I5") (pin "1") (pinfunction "1_1") (pintype "passive"))
      (node (ref "R26") (pin "1") (pinfunction "1_1") (pintype "passive"))
      (node (ref "R28") (pin "2") (pinfunction "2_2") (pintype "passive"))
    )
    (net (code "31") (name "Net-(I9-Pad3)") (class "Default")
      (node (ref "I9") (pin "3") (pinfunction "3_3") (pintype "passive"))
      (node (ref "R30") (pin "1") (pinfunction "1_1") (pintype "passive"))
    )
    (net (code "32") (name "Net-(U1-BOOT0)") (class "Default")
      (node (ref "R2") (pin "2") (pinfunction "2_2") (pintype "passive"))
      (node (ref "U1") (pin "138") (pinfunction "BOOT0_138") (pintype "passive"))
    )
    (net (code "33") (name "Net-(U1-PA5)") (class "Default")
      (node (ref "R9") (pin "1") (pinfunction "1_1") (pintype "passive"))
      (node (ref "U1") (pin "41") (pinfunction "PA5_41") (pintype "passive"))
    )
    (net (code "34") (name "Net-(U1-PA7)") (class "Default")
      (node (ref "R14") (pin "1") (pinfunction "1_1") (pintype "passive"))
      (node (ref "U1") (pin "43") (pinfunction "PA7_43") (pintype "passive"))
    )
    (net (code "35") (name "Net-(U1-PA9)") (class "Default")
      (node (ref "R12") (pin "2") (pinfunction "2_2") (pintype "passive"))
      (node (ref "U1") (pin "101") (pinfunction "PA9_101") (pintype "passive"))
    )
    (net (code "36") (name "Net-(U1-PA12)") (class "Default")
      (node (ref "R10") (pin "2") (pinfunction "2_2") (pintype "passive"))
      (node (ref "U1") (pin "104") (pinfunction "PA12_104") (pintype "passive"))
    )
    (net (code "37") (name "Net-(U1-PB6)") (class "Default")
      (node (ref "R4") (pin "2") (pinfunction "2_2") (pintype "passive"))
      (node (ref "U1") (pin "136") (pinfunction "PB6_136") (pintype "passive"))
    )
    (net (code "38") (name "Net-(U1-PB7)") (class "Default")
      (node (ref "R3") (pin "2") (pinfunction "2_2") (pintype "passive"))
      (node (ref "U1") (pin "137") (pinfunction "PB7_137") (pintype "passive"))
    )
    (net (code "39") (name "Net-(U1-PC6)") (class "Default")
      (node (ref "R15") (pin "2") (pinfunction "2_2") (pintype "passive"))
      (node (ref "U1") (pin "96") (pinfunction "PC6_96") (pintype "passive"))
    )
    (net (code "40") (name "Net-(U1-VCAP_1)") (class "Default")
      (node (ref "C16") (pin "2") (pinfunction "2_2") (pintype "passive"))
      (node (ref "U1") (pin "71") (pinfunction "VCAP_1_71") (pintype "passive"))
    )
    (net (code "41") (name "Net-(U1-VCAP_2)") (class "Default")
      (node (ref "C22") (pin "1") (pinfunction "1_1") (pintype "passive"))
      (node (ref "U1") (pin "106") (pinfunction "VCAP_2_106") (pintype "passive"))
    )
    (net (code "42") (name "Net-(U2-BS)") (class "Default")
      (node (ref "C28") (pin "1") (pinfunction "1_1") (pintype "passive"))
      (node (ref "U2") (pin "1") (pinfunction "BS_1") (pintype "passive"))
    )
    (net (code "43") (name "Net-(U2-FB)") (class "Default")
      (node (ref "C27") (pin "1") (pinfunction "1_1") (pintype "passive"))
      (node (ref "R13") (pin "2") (pinfunction "2_2") (pintype "passive"))
      (node (ref "R8") (pin "1") (pinfunction "1_1") (pintype "passive"))
      (node (ref "U2") (pin "3") (pinfunction "FB_3") (pintype "passive"))
    )
    (net (code "44") (name "Net-(U2-SW)") (class "Default")
      (node (ref "C28") (pin "2") (pinfunction "2_2") (pintype "passive"))
      (node (ref "L1") (pin "2") (pinfunction "2_2") (pintype "passive"))
      (node (ref "U2") (pin "6") (pinfunction "SW_6") (pintype "passive"))
    )
    (net (code "45") (name "Net-(U3-FB)") (class "Default")
      (node (ref "C31") (pin "1") (pinfunction "1_1") (pintype "passive"))
      (node (ref "R17") (pin "1") (pinfunction "1_1") (pintype "passive"))
      (node (ref "R18") (pin "2") (pinfunction "2_2") (pintype "passive"))
      (node (ref "U3") (pin "5") (pinfunction "FB_5") (pintype "passive"))
    )
    (net (code "46") (name "Net-(U3-LX)") (class "Default")
      (node (ref "L2") (pin "1") (pinfunction "1_1") (pintype "passive"))
      (node (ref "U3") (pin "3") (pinfunction "LX_3") (pintype "passive"))
    )
    (net (code "47") (name "Net-(U4-CANH)") (class "Default")
      (node (ref "R19") (pin "2") (pinfunction "2_2") (pintype "passive"))
      (node (ref "R20") (pin "2") (pinfunction "2_2") (pintype "passive"))
      (node (ref "U4") (pin "7") (pinfunction "CANH_7") (pintype "passive"))
    )
    (net (code "48") (name "Net-(U4-CANL)") (class "Default")
      (node (ref "R20") (pin "1") (pinfunction "1_1") (pintype "passive"))
      (node (ref "R21") (pin "2") (pinfunction "2_2") (pintype "passive"))
      (node (ref "U4") (pin "6") (pinfunction "CANL_6") (pintype "passive"))
    )
    (net (code "49") (name "Net-(U4-RXD)") (class "Default")
      (node (ref "R22") (pin "2") (pinfunction "2_2") (pintype "passive"))
      (node (ref "U4") (pin "4") (pinfunction "RXD_4") (pintype "passive"))
    )
    (net (code "50") (name "VCC") (class "Default")
      (node (ref "C23") (pin "1") (pinfunction "1_1") (pintype "passive"))
      (node (ref "C29") (pin "1") (pinfunction "1_1") (pintype "passive"))
      (node (ref "C30") (pin "1") (pinfunction "1_1") (pintype "passive"))
      (node (ref "D1") (pin "1") (pinfunction "K_1") (pintype "passive"))
      (node (ref "I1") (pin "2") (pinfunction "2_2") (pintype "passive"))
      (node (ref "U2") (pin "4") (pinfunction "EN_4") (pintype "passive"))
      (node (ref "U2") (pin "5") (pinfunction "IN_5") (pintype "passive"))
    )
    (net (code "51") (name "unconnected-(I1-Pad3)") (class "Default")
      (node (ref "I1") (pin "3") (pinfunction "3_3") (pintype "passive"))
    )
    (net (code "52") (name "unconnected-(I1-Pad4)") (class "Default")
      (node (ref "I1") (pin "4") (pinfunction "4_4") (pintype "passive"))
    )
    (net (code "53") (name "unconnected-(S1-Pad2)") (class "Default")
      (node (ref "S1") (pin "2") (pinfunction "2_2") (pintype "passive"))
    )
    (net (code "54") (name "unconnected-(S1-Pad3)") (class "Default")
      (node (ref "S1") (pin "3") (pinfunction "3_3") (pintype "passive"))
    )
    (net (code "55") (name "unconnected-(U1-PA0-Pad34)") (class "Default")
      (node (ref "U1") (pin "34") (pinfunction "PA0_34") (pintype "passive"))
    )
    (net (code "56") (name "unconnected-(U1-PA1-Pad35)") (class "Default")
      (node (ref "U1") (pin "35") (pinfunction "PA1_35") (pintype "passive"))
    )
    (net (code "57") (name "unconnected-(U1-PA2-Pad36)") (class "Default")
      (node (ref "U1") (pin "36") (pinfunction "PA2_36") (pintype "passive"))
    )
    (net (code "58") (name "unconnected-(U1-PA3-Pad37)") (class "Default")
      (node (ref "U1") (pin "37") (pinfunction "PA3_37") (pintype "passive"))
    )
    (net (code "59") (name "unconnected-(U1-PA4-Pad40)") (class "Default")
      (node (ref "U1") (pin "40") (pinfunction "PA4_40") (pintype "passive"))
    )
    (net (code "60") (name "unconnected-(U1-PA8-Pad100)") (class "Default")
      (node (ref "U1") (pin "100") (pinfunction "PA8_100") (pintype "passive"))
    )
    (net (code "61") (name "unconnected-(U1-PA15-Pad110)") (class "Default")
      (node (ref "U1") (pin "110") (pinfunction "PA15_110") (pintype "passive"))
    )
    (net (code "62") (name "unconnected-(U1-PB0-Pad46)") (class "Default")
      (node (ref "U1") (pin "46") (pinfunction "PB0_46") (pintype "passive"))
    )
    (net (code "63") (name "unconnected-(U1-PB1-Pad47)") (class "Default")
      (node (ref "U1") (pin "47") (pinfunction "PB1_47") (pintype "passive"))
    )
    (net (code "64") (name "unconnected-(U1-PB2-Pad48)") (class "Default")
      (node (ref "U1") (pin "48") (pinfunction "PB2_48") (pintype "passive"))
    )
    (net (code "65") (name "unconnected-(U1-PB3-Pad133)") (class "Default")
      (node (ref "U1") (pin "133") (pinfunction "PB3_133") (pintype "passive"))
    )
    (net (code "66") (name "unconnected-(U1-PB4-Pad134)") (class "Default")
      (node (ref "U1") (pin "134") (pinfunction "PB4_134") (pintype "passive"))
    )
    (net (code "67") (name "unconnected-(U1-PB5-Pad135)") (class "Default")
      (node (ref "U1") (pin "135") (pinfunction "PB5_135") (pintype "passive"))
    )
    (net (code "68") (name "unconnected-(U1-PB8-Pad139)") (class "Default")
      (node (ref "U1") (pin "139") (pinfunction "PB8_139") (pintype "passive"))
    )
    (net (code "69") (name "unconnected-(U1-PB9-Pad140)") (class "Default")
      (node (ref "U1") (pin "140") (pinfunction "PB9_140") (pintype "passive"))
    )
    (net (code "70") (name "unconnected-(U1-PB10-Pad69)") (class "Default")
      (node (ref "U1") (pin "69") (pinfunction "PB10_69") (pintype "passive"))
    )
    (net (code "71") (name "unconnected-(U1-PB11-Pad70)") (class "Default")
      (node (ref "U1") (pin "70") (pinfunction "PB11_70") (pintype "passive"))
    )
    (net (code "72") (name "unconnected-(U1-PB12-Pad73)") (class "Default")
      (node (ref "U1") (pin "73") (pinfunction "PB12_73") (pintype "passive"))
    )
    (net (code "73") (name "unconnected-(U1-PB13-Pad74)") (class "Default")
      (node (ref "U1") (pin "74") (pinfunction "PB13_74") (pintype "passive"))
    )
    (net (code "74") (name "unconnected-(U1-PB14-Pad75)") (class "Default")
      (node (ref "U1") (pin "75") (pinfunction "PB14_75") (pintype "passive"))
    )
    (net (code "75") (name "unconnected-(U1-PB15-Pad76)") (class "Default")
      (node (ref "U1") (pin "76") (pinfunction "PB15_76") (pintype "passive"))
    )
    (net (code "76") (name "unconnected-(U1-PC0-Pad26)") (class "Default")
      (node (ref "U1") (pin "26") (pinfunction "PC0_26") (pintype "passive"))
    )
    (net (code "77") (name "unconnected-(U1-PC1-Pad27)") (class "Default")
      (node (ref "U1") (pin "27") (pinfunction "PC1_27") (pintype "passive"))
    )
    (net (code "78") (name "unconnected-(U1-PC2-Pad28)") (class "Default")
      (node (ref "U1") (pin "28") (pinfunction "PC2_28") (pintype "passive"))
    )
    (net (code "79") (name "unconnected-(U1-PC3-Pad29)") (class "Default")
      (node (ref "U1") (pin "29") (pinfunction "PC3_29") (pintype "passive"))
    )
    (net (code "80") (name "unconnected-(U1-PC4-Pad44)") (class "Default")
      (node (ref "U1") (pin "44") (pinfunction "PC4_44") (pintype "passive"))
    )
    (net (code "81") (name "unconnected-(U1-PC5-Pad45)") (class "Default")
      (node (ref "U1") (pin "45") (pinfunction "PC5_45") (pintype "passive"))
    )
    (net (code "82") (name "unconnected-(U1-PC8-Pad98)") (class "Default")
      (node (ref "U1") (pin "98") (pinfunction "PC8_98") (pintype "passive"))
    )
    (net (code "83") (name "unconnected-(U1-PC9-Pad99)") (class "Default")
      (node (ref "U1") (pin "99") (pinfunction "PC9_99") (pintype "passive"))
    )
    (net (code "84") (name "unconnected-(U1-PC10-Pad111)") (class "Default")
      (node (ref "U1") (pin "111") (pinfunction "PC10_111") (pintype "passive"))
    )
    (net (code "85") (name "unconnected-(U1-PC11-Pad112)") (class "Default")
      (node (ref "U1") (pin "112") (pinfunction "PC11_112") (pintype "passive"))
    )
    (net (code "86") (name "unconnected-(U1-PC12-Pad113)") (class "Default")
      (node (ref "U1") (pin "113") (pinfunction "PC12_113") (pintype "passive"))
    )
    (net (code "87") (name "unconnected-(U1-PC13-Pad7)") (class "Default")
      (node (ref "U1") (pin "7") (pinfunction "PC13_7") (pintype "passive"))
    )
    (net (code "88") (name "unconnected-(U1-PC14-Pad8)") (class "Default")
      (node (ref "U1") (pin "8") (pinfunction "PC14_8") (pintype "passive"))
    )
    (net (code "89") (name "unconnected-(U1-PC15-Pad9)") (class "Default")
      (node (ref "U1") (pin "9") (pinfunction "PC15_9") (pintype "passive"))
    )
    (net (code "90") (name "unconnected-(U1-PD0-Pad114)") (class "Default")
      (node (ref "U1") (pin "114") (pinfunction "PD0_114") (pintype "passive"))
    )
    (net (code "91") (name "unconnected-(U1-PD1-Pad115)") (class "Default")
      (node (ref "U1") (pin "115") (pinfunction "PD1_115") (pintype "passive"))
    )
    (net (code "92") (name "unconnected-(U1-PD2-Pad116)") (class "Default")
      (node (ref "U1") (pin "116") (pinfunction "PD2_116") (pintype "passive"))
    )
    (net (code "93") (name "unconnected-(U1-PD3-Pad117)") (class "Default")
      (node (ref "U1") (pin "117") (pinfunction "PD3_117") (pintype "passive"))
    )
    (net (code "94") (name "unconnected-(U1-PD4-Pad118)") (class "Default")
      (node (ref "U1") (pin "118") (pinfunction "PD4_118") (pintype "passive"))
    )
    (net (code "95") (name "unconnected-(U1-PD5-Pad119)") (class "Default")
      (node (ref "U1") (pin "119") (pinfunction "PD5_119") (pintype "passive"))
    )
    (net (code "96") (name "unconnected-(U1-PD6-Pad122)") (class "Default")
      (node (ref "U1") (pin "122") (pinfunction "PD6_122") (pintype "passive"))
    )
    (net (code "97") (name "unconnected-(U1-PD7-Pad123)") (class "Default")
      (node (ref "U1") (pin "123") (pinfunction "PD7_123") (pintype "passive"))
    )
    (net (code "98") (name "unconnected-(U1-PD8-Pad77)") (class "Default")
      (node (ref "U1") (pin "77") (pinfunction "PD8_77") (pintype "passive"))
    )
    (net (code "99") (name "unconnected-(U1-PD9-Pad78)") (class "Default")
      (node (ref "U1") (pin "78") (pinfunction "PD9_78") (pintype "passive"))
    )
    (net (code "100") (name "unconnected-(U1-PD11-Pad80)") (class "Default")
      (node (ref "U1") (pin "80") (pinfunction "PD11_80") (pintype "passive"))
    )
    (net (code "101") (name "unconnected-(U1-PD12-Pad81)") (class "Default")
      (node (ref "U1") (pin "81") (pinfunction "PD12_81") (pintype "passive"))
    )
    (net (code "102") (name "unconnected-(U1-PD13-Pad82)") (class "Default")
      (node (ref "U1") (pin "82") (pinfunction "PD13_82") (pintype "passive"))
    )
    (net (code "103") (name "unconnected-(U1-PD14-Pad85)") (class "Default")
      (node (ref "U1") (pin "85") (pinfunction "PD14_85") (pintype "passive"))
    )
    (net (code "104") (name "unconnected-(U1-PD15-Pad86)") (class "Default")
      (node (ref "U1") (pin "86") (pinfunction "PD15_86") (pintype "passive"))
    )
    (net (code "105") (name "unconnected-(U1-PE0-Pad141)") (class "Default")
      (node (ref "U1") (pin "141") (pinfunction "PE0_141") (pintype "passive"))
    )
    (net (code "106") (name "unconnected-(U1-PE1-Pad142)") (class "Default")
      (node (ref "U1") (pin "142") (pinfunction "PE1_142") (pintype "passive"))
    )
    (net (code "107") (name "unconnected-(U1-PE2-Pad1)") (class "Default")
      (node (ref "U1") (pin "1") (pinfunction "PE2_1") (pintype "passive"))
    )
    (net (code "108") (name "unconnected-(U1-PE3-Pad2)") (class "Default")
      (node (ref "U1") (pin "2") (pinfunction "PE3_2") (pintype "passive"))
    )
    (net (code "109") (name "unconnected-(U1-PE4-Pad3)") (class "Default")
      (node (ref "U1") (pin "3") (pinfunction "PE4_3") (pintype "passive"))
    )
    (net (code "110") (name "unconnected-(U1-PE5-Pad4)") (class "Default")
      (node (ref "U1") (pin "4") (pinfunction "PE5_4") (pintype "passive"))
    )
    (net (code "111") (name "unconnected-(U1-PE6-Pad5)") (class "Default")
      (node (ref "U1") (pin "5") (pinfunction "PE6_5") (pintype "passive"))
    )
    (net (code "112") (name "unconnected-(U1-PE7-Pad58)") (class "Default")
      (node (ref "U1") (pin "58") (pinfunction "PE7_58") (pintype "passive"))
    )
    (net (code "113") (name "unconnected-(U1-PE8-Pad59)") (class "Default")
      (node (ref "U1") (pin "59") (pinfunction "PE8_59") (pintype "passive"))
    )
    (net (code "114") (name "unconnected-(U1-PE10-Pad63)") (class "Default")
      (node (ref "U1") (pin "63") (pinfunction "PE10_63") (pintype "passive"))
    )
    (net (code "115") (name "unconnected-(U1-PE12-Pad65)") (class "Default")
      (node (ref "U1") (pin "65") (pinfunction "PE12_65") (pintype "passive"))
    )
    (net (code "116") (name "unconnected-(U1-PE13-Pad66)") (class "Default")
      (node (ref "U1") (pin "66") (pinfunction "PE13_66") (pintype "passive"))
    )
    (net (code "117") (name "unconnected-(U1-PE14-Pad67)") (class "Default")
      (node (ref "U1") (pin "67") (pinfunction "PE14_67") (pintype "passive"))
    )
    (net (code "118") (name "unconnected-(U1-PE15-Pad68)") (class "Default")
      (node (ref "U1") (pin "68") (pinfunction "PE15_68") (pintype "passive"))
    )
    (net (code "119") (name "unconnected-(U1-PF0-Pad10)") (class "Default")
      (node (ref "U1") (pin "10") (pinfunction "PF0_10") (pintype "passive"))
    )
    (net (code "120") (name "unconnected-(U1-PF1-Pad11)") (class "Default")
      (node (ref "U1") (pin "11") (pinfunction "PF1_11") (pintype "passive"))
    )
    (net (code "121") (name "unconnected-(U1-PF2-Pad12)") (class "Default")
      (node (ref "U1") (pin "12") (pinfunction "PF2_12") (pintype "passive"))
    )
    (net (code "122") (name "unconnected-(U1-PF3-Pad13)") (class "Default")
      (node (ref "U1") (pin "13") (pinfunction "PF3_13") (pintype "passive"))
    )
    (net (code "123") (name "unconnected-(U1-PF4-Pad14)") (class "Default")
      (node (ref "U1") (pin "14") (pinfunction "PF4_14") (pintype "passive"))
    )
    (net (code "124") (name "unconnected-(U1-PF5-Pad15)") (class "Default")
      (node (ref "U1") (pin "15") (pinfunction "PF5_15") (pintype "passive"))
    )
    (net (code "125") (name "unconnected-(U1-PF6-Pad18)") (class "Default")
      (node (ref "U1") (pin "18") (pinfunction "PF6_18") (pintype "passive"))
    )
    (net (code "126") (name "unconnected-(U1-PF7-Pad19)") (class "Default")
      (node (ref "U1") (pin "19") (pinfunction "PF7_19") (pintype "passive"))
    )
    (net (code "127") (name "unconnected-(U1-PF8-Pad20)") (class "Default")
      (node (ref "U1") (pin "20") (pinfunction "PF8_20") (pintype "passive"))
    )
    (net (code "128") (name "unconnected-(U1-PF9-Pad21)") (class "Default")
      (node (ref "U1") (pin "21") (pinfunction "PF9_21") (pintype "passive"))
    )
    (net (code "129") (name "unconnected-(U1-PF10-Pad22)") (class "Default")
      (node (ref "U1") (pin "22") (pinfunction "PF10_22") (pintype "passive"))
    )
    (net (code "130") (name "unconnected-(U1-PF11-Pad49)") (class "Default")
      (node (ref "U1") (pin "49") (pinfunction "PF11_49") (pintype "passive"))
    )
    (net (code "131") (name "unconnected-(U1-PF12-Pad50)") (class "Default")
      (node (ref "U1") (pin "50") (pinfunction "PF12_50") (pintype "passive"))
    )
    (net (code "132") (name "unconnected-(U1-PF13-Pad53)") (class "Default")
      (node (ref "U1") (pin "53") (pinfunction "PF13_53") (pintype "passive"))
    )
    (net (code "133") (name "unconnected-(U1-PF14-Pad54)") (class "Default")
      (node (ref "U1") (pin "54") (pinfunction "PF14_54") (pintype "passive"))
    )
    (net (code "134") (name "unconnected-(U1-PF15-Pad55)") (class "Default")
      (node (ref "U1") (pin "55") (pinfunction "PF15_55") (pintype "passive"))
    )
    (net (code "135") (name "unconnected-(U1-PG0-Pad56)") (class "Default")
      (node (ref "U1") (pin "56") (pinfunction "PG0_56") (pintype "passive"))
    )
    (net (code "136") (name "unconnected-(U1-PG1-Pad57)") (class "Default")
      (node (ref "U1") (pin "57") (pinfunction "PG1_57") (pintype "passive"))
    )
    (net (code "137") (name "unconnected-(U1-PG2-Pad87)") (class "Default")
      (node (ref "U1") (pin "87") (pinfunction "PG2_87") (pintype "passive"))
    )
    (net (code "138") (name "unconnected-(U1-PG3-Pad88)") (class "Default")
      (node (ref "U1") (pin "88") (pinfunction "PG3_88") (pintype "passive"))
    )
    (net (code "139") (name "unconnected-(U1-PG4-Pad89)") (class "Default")
      (node (ref "U1") (pin "89") (pinfunction "PG4_89") (pintype "passive"))
    )
    (net (code "140") (name "unconnected-(U1-PG5-Pad90)") (class "Default")
      (node (ref "U1") (pin "90") (pinfunction "PG5_90") (pintype "passive"))
    )
    (net (code "141") (name "unconnected-(U1-PG6-Pad91)") (class "Default")
      (node (ref "U1") (pin "91") (pinfunction "PG6_91") (pintype "passive"))
    )
    (net (code "142") (name "unconnected-(U1-PG7-Pad92)") (class "Default")
      (node (ref "U1") (pin "92") (pinfunction "PG7_92") (pintype "passive"))
    )
    (net (code "143") (name "unconnected-(U1-PG8-Pad93)") (class "Default")
      (node (ref "U1") (pin "93") (pinfunction "PG8_93") (pintype "passive"))
    )
    (net (code "144") (name "unconnected-(U1-PG9-Pad124)") (class "Default")
      (node (ref "U1") (pin "124") (pinfunction "PG9_124") (pintype "passive"))
    )
    (net (code "145") (name "unconnected-(U1-PG10-Pad125)") (class "Default")
      (node (ref "U1") (pin "125") (pinfunction "PG10_125") (pintype "passive"))
    )
    (net (code "146") (name "unconnected-(U1-PG11-Pad126)") (class "Default")
      (node (ref "U1") (pin "126") (pinfunction "PG11_126") (pintype "passive"))
    )
    (net (code "147") (name "unconnected-(U1-PG12-Pad127)") (class "Default")
      (node (ref "U1") (pin "127") (pinfunction "PG12_127") (pintype "passive"))
    )
    (net (code "148") (name "unconnected-(U1-PG13-Pad128)") (class "Default")
      (node (ref "U1") (pin "128") (pinfunction "PG13_128") (pintype "passive"))
    )
    (net (code "149") (name "unconnected-(U1-PG14-Pad129)") (class "Default")
      (node (ref "U1") (pin "129") (pinfunction "PG14_129") (pintype "passive"))
    )
    (net (code "150") (name "unconnected-(U1-PG15-Pad132)") (class "Default")
      (node (ref "U1") (pin "132") (pinfunction "PG15_132") (pintype "passive"))
    )
  )
)
